# BiodataModular_007.net
KiCad netlist of a schematic drawn in EAGLE
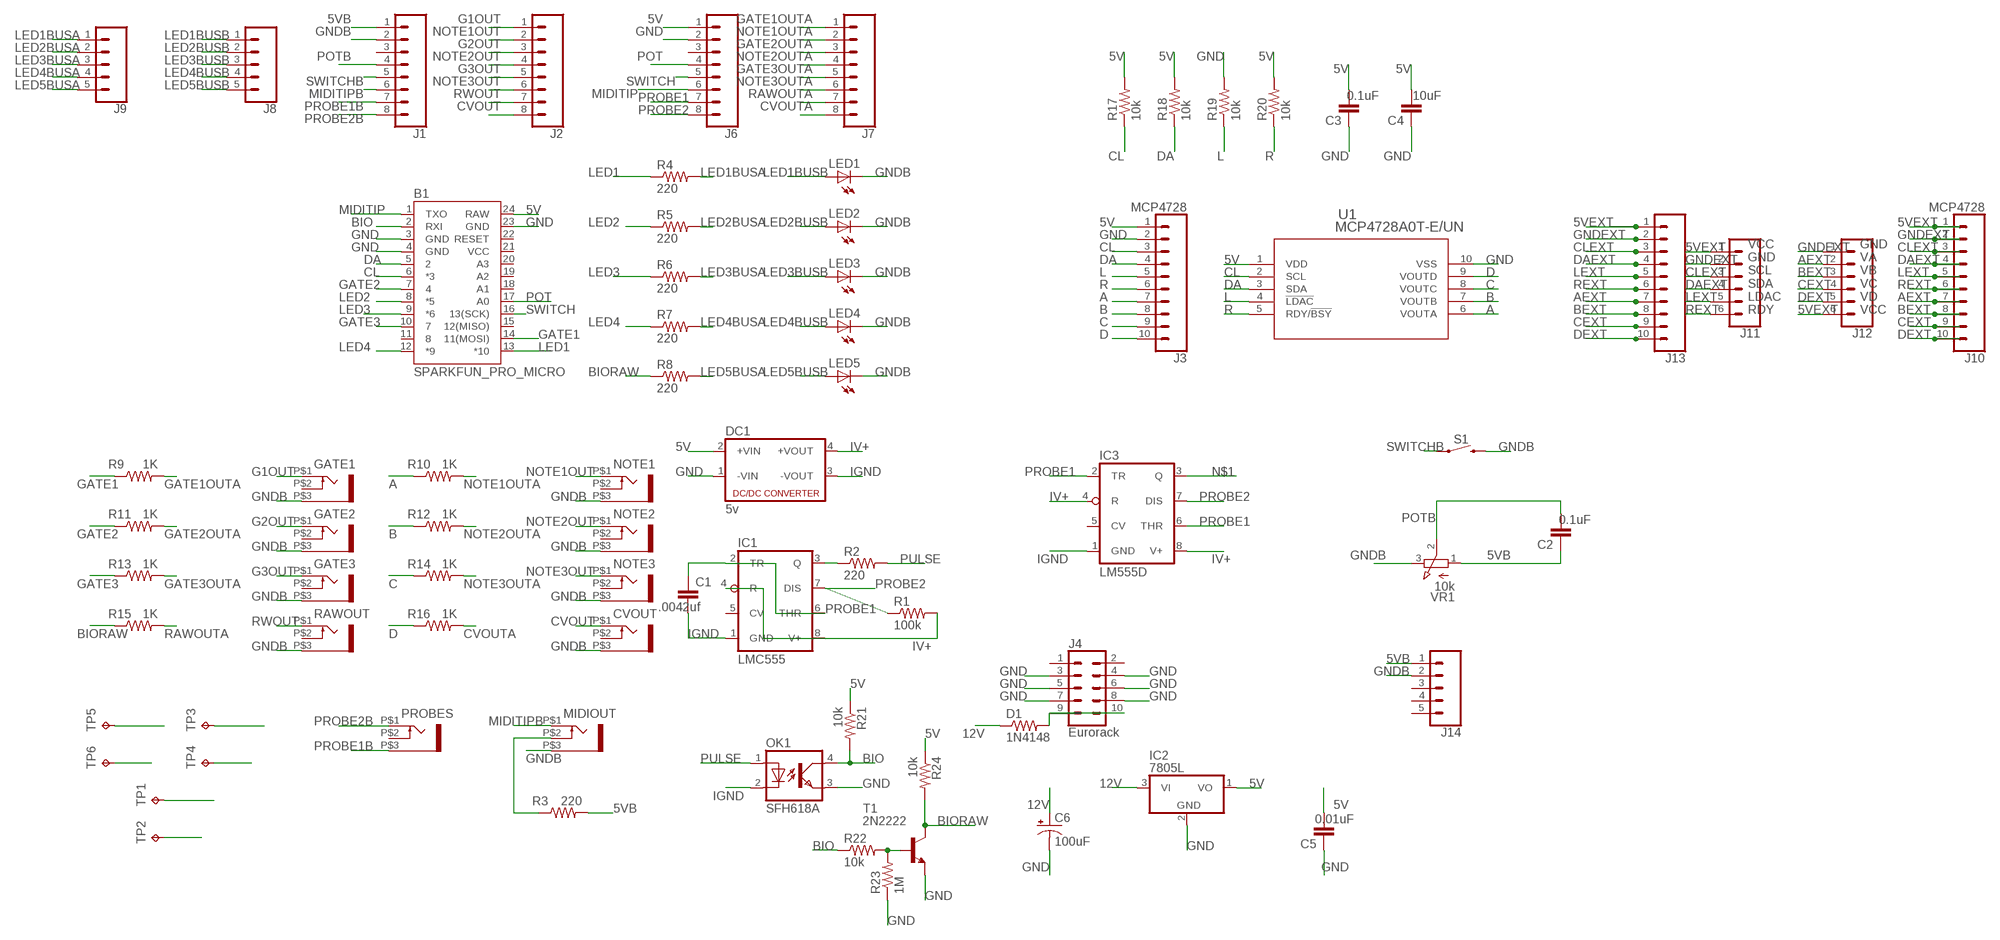
[diagram p0: schematic, sheet 1]

(export (version "E")
  (design (tool "Eeschema 10.0.6"))
  (components
    (comp (ref "B1")
      (value "SPARKFUN_PRO_MICRO")
      (footprint "eagle-import:SPARKFUN_PRO_MICRO")
      (libsource (lib "eagle-import") (part "SPARKFUN_PRO_MICRO"))
    )
    (comp (ref "C1")
      (value ".0042uf")
      (footprint "eagle-import:C2.5-2")
      (libsource (lib "eagle-import") (part "C2.5/2"))
    )
    (comp (ref "C2")
      (value "0.1uF")
      (footprint "eagle-import:C2.5-2")
      (libsource (lib "eagle-import") (part "C2.5/2"))
    )
    (comp (ref "C3")
      (value "0.1uF")
      (footprint "eagle-import:C2.5-2")
      (libsource (lib "eagle-import") (part "C2.5/2"))
    )
    (comp (ref "C4")
      (value "10uF")
      (footprint "eagle-import:C2.5-2")
      (libsource (lib "eagle-import") (part "C2.5/2"))
    )
    (comp (ref "C5")
      (value "0.01uF")
      (footprint "eagle-import:C2.5-2")
      (libsource (lib "eagle-import") (part "C2.5/2"))
    )
    (comp (ref "C6")
      (value "100uF")
      (footprint "eagle-import:B45181A")
      (libsource (lib "eagle-import") (part "CPOL-USB45181A"))
    )
    (comp (ref "CVOUT")
      (value "WQP-PJ301M-12_JACK")
      (footprint "eagle-import:WQP-PJ301M-12_JACK")
      (libsource (lib "eagle-import") (part "WQP-PJ301M-12_JACK"))
    )
    (comp (ref "D1")
      (value "1N4148")
      (footprint "eagle-import:0204V")
      (libsource (lib "eagle-import") (part "R-US_0204/2V"))
    )
    (comp (ref "DC1")
      (value "5v")
      (footprint "eagle-import:NME")
      (fields (field (name "MF") "C & D TECHNOLOGIES, INC") (field (name "MPN") "NME1205D"))
      (libsource (lib "eagle-import") (part "NME"))
    )
    (comp (ref "GATE1")
      (value "WQP-PJ301M-12_JACK")
      (footprint "eagle-import:WQP-PJ301M-12_JACK")
      (libsource (lib "eagle-import") (part "WQP-PJ301M-12_JACK"))
    )
    (comp (ref "GATE2")
      (value "WQP-PJ301M-12_JACK")
      (footprint "eagle-import:WQP-PJ301M-12_JACK")
      (libsource (lib "eagle-import") (part "WQP-PJ301M-12_JACK"))
    )
    (comp (ref "GATE3")
      (value "WQP-PJ301M-12_JACK")
      (footprint "eagle-import:WQP-PJ301M-12_JACK")
      (libsource (lib "eagle-import") (part "WQP-PJ301M-12_JACK"))
    )
    (comp (ref "IC1")
      (value "LMC555")
      (footprint "eagle-import:DIL08")
      (libsource (lib "eagle-import") (part "linear_555NLM"))
    )
    (comp (ref "IC2")
      (value "7805L")
      (footprint "eagle-import:TO92")
      (libsource (lib "eagle-import") (part "78L05"))
    )
    (comp (ref "IC3")
      (value "LM555D")
      (footprint "eagle-import:SO08")
      (libsource (lib "eagle-import") (part "555DLM"))
    )
    (comp (ref "J1")
      (value "CONN_08\"")
      (footprint "eagle-import:1X08")
      (libsource (lib "eagle-import") (part "CONN_08{dblquote}"))
    )
    (comp (ref "J2")
      (value "CONN_08\"")
      (footprint "eagle-import:1X08")
      (libsource (lib "eagle-import") (part "CONN_08{dblquote}"))
    )
    (comp (ref "J3")
      (value "MCP4728")
      (footprint "eagle-import:1X10")
      (libsource (lib "eagle-import") (part "CONN_10{dblquote}"))
    )
    (comp (ref "J4")
      (value "Eurorack")
      (footprint "eagle-import:2X5")
      (libsource (lib "eagle-import") (part "CONN_05X2PTH"))
    )
    (comp (ref "J6")
      (value "CONN_08\"")
      (footprint "eagle-import:1X08")
      (libsource (lib "eagle-import") (part "CONN_08{dblquote}"))
    )
    (comp (ref "J7")
      (value "CONN_08\"")
      (footprint "eagle-import:1X08")
      (libsource (lib "eagle-import") (part "CONN_08{dblquote}"))
    )
    (comp (ref "J8")
      (value "CONN_05")
      (footprint "eagle-import:1X05")
      (libsource (lib "eagle-import") (part "CONN_05"))
    )
    (comp (ref "J9")
      (value "CONN_05")
      (footprint "eagle-import:1X05")
      (libsource (lib "eagle-import") (part "CONN_05"))
    )
    (comp (ref "J10")
      (value "MCP4728")
      (footprint "eagle-import:1X10")
      (libsource (lib "eagle-import") (part "CONN_10{dblquote}"))
    )
    (comp (ref "J11")
      (value "CONN_06SILK_FEMALE_PTH")
      (footprint "eagle-import:1X06")
      (libsource (lib "eagle-import") (part "CONN_06SILK_FEMALE_PTH"))
    )
    (comp (ref "J12")
      (value "CONN_06SILK_FEMALE_PTH")
      (footprint "eagle-import:1X06")
      (libsource (lib "eagle-import") (part "CONN_06SILK_FEMALE_PTH"))
    )
    (comp (ref "J13")
      (value "CONN_10SMD_MALE")
      (footprint "eagle-import:1X10_SMD_MALE")
      (libsource (lib "eagle-import") (part "CONN_10SMD_MALE"))
    )
    (comp (ref "J14")
      (value "CONN_05")
      (footprint "eagle-import:1X05")
      (libsource (lib "eagle-import") (part "CONN_05"))
    )
    (comp (ref "LED1")
      (value "LED3MM")
      (footprint "eagle-import:LED3MM")
      (libsource (lib "eagle-import") (part "LED3MM"))
    )
    (comp (ref "LED2")
      (value "LED3MM")
      (footprint "eagle-import:LED3MM")
      (libsource (lib "eagle-import") (part "LED3MM"))
    )
    (comp (ref "LED3")
      (value "LED3MM")
      (footprint "eagle-import:LED3MM")
      (libsource (lib "eagle-import") (part "LED3MM"))
    )
    (comp (ref "LED4")
      (value "LED3MM")
      (footprint "eagle-import:LED3MM")
      (libsource (lib "eagle-import") (part "LED3MM"))
    )
    (comp (ref "LED5")
      (value "LED3MM")
      (footprint "eagle-import:LED3MM")
      (libsource (lib "eagle-import") (part "LED3MM"))
    )
    (comp (ref "MIDIOUT")
      (value "WQP-PJ301M-12_JACK")
      (footprint "eagle-import:WQP-PJ301M-12_JACK")
      (libsource (lib "eagle-import") (part "WQP-PJ301M-12_JACK"))
    )
    (comp (ref "NOTE1")
      (value "WQP-PJ301M-12_JACK")
      (footprint "eagle-import:WQP-PJ301M-12_JACK")
      (libsource (lib "eagle-import") (part "WQP-PJ301M-12_JACK"))
    )
    (comp (ref "NOTE2")
      (value "WQP-PJ301M-12_JACK")
      (footprint "eagle-import:WQP-PJ301M-12_JACK")
      (libsource (lib "eagle-import") (part "WQP-PJ301M-12_JACK"))
    )
    (comp (ref "NOTE3")
      (value "WQP-PJ301M-12_JACK")
      (footprint "eagle-import:WQP-PJ301M-12_JACK")
      (libsource (lib "eagle-import") (part "WQP-PJ301M-12_JACK"))
    )
    (comp (ref "OK1")
      (value "SFH618A")
      (footprint "eagle-import:DIP4")
      (fields (field (name "MF") "VISHAY/TELEFUNKEN") (field (name "MPN") "SFH618A-5"))
      (libsource (lib "eagle-import") (part "SFH618?A-5"))
    )
    (comp (ref "PROBES")
      (value "WQP-PJ301M-12_JACK")
      (footprint "eagle-import:WQP-PJ301M-12_JACK")
      (libsource (lib "eagle-import") (part "WQP-PJ301M-12_JACK"))
    )
    (comp (ref "R1")
      (value "100k")
      (footprint "eagle-import:0204V")
      (libsource (lib "eagle-import") (part "R-US_0204/2V"))
    )
    (comp (ref "R2")
      (value "220")
      (footprint "eagle-import:0204V")
      (libsource (lib "eagle-import") (part "R-US_0204/2V"))
    )
    (comp (ref "R3")
      (value "220")
      (footprint "eagle-import:0204V")
      (libsource (lib "eagle-import") (part "R-US_0204/2V"))
    )
    (comp (ref "R4")
      (value "220")
      (footprint "eagle-import:0204V")
      (libsource (lib "eagle-import") (part "R-US_0204/2V"))
    )
    (comp (ref "R5")
      (value "220")
      (footprint "eagle-import:0204V")
      (libsource (lib "eagle-import") (part "R-US_0204/2V"))
    )
    (comp (ref "R6")
      (value "220")
      (footprint "eagle-import:0204V")
      (libsource (lib "eagle-import") (part "R-US_0204/2V"))
    )
    (comp (ref "R7")
      (value "220")
      (footprint "eagle-import:0204V")
      (libsource (lib "eagle-import") (part "R-US_0204/2V"))
    )
    (comp (ref "R8")
      (value "220")
      (footprint "eagle-import:0204V")
      (libsource (lib "eagle-import") (part "R-US_0204/2V"))
    )
    (comp (ref "R9")
      (value "1K")
      (footprint "eagle-import:0204V")
      (libsource (lib "eagle-import") (part "R-US_0204/2V"))
    )
    (comp (ref "R10")
      (value "1K")
      (footprint "eagle-import:0204V")
      (libsource (lib "eagle-import") (part "R-US_0204/2V"))
    )
    (comp (ref "R11")
      (value "1K")
      (footprint "eagle-import:0204V")
      (libsource (lib "eagle-import") (part "R-US_0204/2V"))
    )
    (comp (ref "R12")
      (value "1K")
      (footprint "eagle-import:0204V")
      (libsource (lib "eagle-import") (part "R-US_0204/2V"))
    )
    (comp (ref "R13")
      (value "1K")
      (footprint "eagle-import:0204V")
      (libsource (lib "eagle-import") (part "R-US_0204/2V"))
    )
    (comp (ref "R14")
      (value "1K")
      (footprint "eagle-import:0204V")
      (libsource (lib "eagle-import") (part "R-US_0204/2V"))
    )
    (comp (ref "R15")
      (value "1K")
      (footprint "eagle-import:0204V")
      (libsource (lib "eagle-import") (part "R-US_0204/2V"))
    )
    (comp (ref "R16")
      (value "1K")
      (footprint "eagle-import:0204V")
      (libsource (lib "eagle-import") (part "R-US_0204/2V"))
    )
    (comp (ref "R17")
      (value "10k")
      (footprint "eagle-import:0204V")
      (libsource (lib "eagle-import") (part "R-US_0204/2V"))
    )
    (comp (ref "R18")
      (value "10k")
      (footprint "eagle-import:0204V")
      (libsource (lib "eagle-import") (part "R-US_0204/2V"))
    )
    (comp (ref "R19")
      (value "10k")
      (footprint "eagle-import:0204V")
      (libsource (lib "eagle-import") (part "R-US_0204/2V"))
    )
    (comp (ref "R20")
      (value "10k")
      (footprint "eagle-import:0204V")
      (libsource (lib "eagle-import") (part "R-US_0204/2V"))
    )
    (comp (ref "R21")
      (value "10k")
      (footprint "eagle-import:0204V")
      (libsource (lib "eagle-import") (part "R-US_0204/2V"))
    )
    (comp (ref "R22")
      (value "10k")
      (footprint "eagle-import:0204V")
      (libsource (lib "eagle-import") (part "R-US_0204/2V"))
    )
    (comp (ref "R23")
      (value "1M")
      (footprint "eagle-import:0204V")
      (libsource (lib "eagle-import") (part "R-US_0204/2V"))
    )
    (comp (ref "R24")
      (value "10k")
      (footprint "eagle-import:0204V")
      (libsource (lib "eagle-import") (part "R-US_0204/2V"))
    )
    (comp (ref "RAWOUT")
      (value "WQP-PJ301M-12_JACK")
      (footprint "eagle-import:WQP-PJ301M-12_JACK")
      (libsource (lib "eagle-import") (part "WQP-PJ301M-12_JACK"))
    )
    (comp (ref "S1")
      (value "MOMENTARY-SWITCH-SPST-PTH-6.0MM")
      (footprint "eagle-import:TACTILE_SWITCH_PTH_6.0MM")
      (libsource (lib "eagle-import") (part "MOMENTARY-SWITCH-SPST-PTH-6.0MM"))
    )
    (comp (ref "T1")
      (value "2N2222")
      (footprint "eagle-import:TO92-EBC-OVAL")
      (libsource (lib "eagle-import") (part "2N2222"))
    )
    (comp (ref "TP1")
      (value "TPB1,27")
      (footprint "eagle-import:B1,27")
      (libsource (lib "eagle-import") (part "TPB1,27"))
    )
    (comp (ref "TP2")
      (value "TPB1,27")
      (footprint "eagle-import:B1,27")
      (libsource (lib "eagle-import") (part "TPB1,27"))
    )
    (comp (ref "TP3")
      (value "TPB1,27")
      (footprint "eagle-import:B1,27")
      (libsource (lib "eagle-import") (part "TPB1,27"))
    )
    (comp (ref "TP4")
      (value "TPB1,27")
      (footprint "eagle-import:B1,27")
      (libsource (lib "eagle-import") (part "TPB1,27"))
    )
    (comp (ref "TP5")
      (value "TPB1,27")
      (footprint "eagle-import:B1,27")
      (libsource (lib "eagle-import") (part "TPB1,27"))
    )
    (comp (ref "TP6")
      (value "TPB1,27")
      (footprint "eagle-import:B1,27")
      (libsource (lib "eagle-import") (part "TPB1,27"))
    )
    (comp (ref "U1")
      (value "MCP4728A0T-E/UN")
      (footprint "eagle-import:MSOP10_MC")
      (fields (field (name "MANUFACTURER_PART_NUMBER") "MCP4728A0TEUN"))
      (libsource (lib "eagle-import") (part "MCP4728A0T-E/UN"))
    )
    (comp (ref "VR1")
      (value "10k")
      (footprint "eagle-import:EVUF")
      (libsource (lib "eagle-import") (part "EVUAF2"))
    )
  )
  (nets
    (net (code "1") (name "/5V") (class "Default")
      (node (ref "B1") (pin "24") (pinfunction "RAW_24") (pintype "power_in"))
      (node (ref "C3") (pin "2") (pinfunction "2_2") (pintype "passive"))
      (node (ref "C4") (pin "2") (pinfunction "2_2") (pintype "passive"))
      (node (ref "C5") (pin "2") (pinfunction "2_2") (pintype "passive"))
      (node (ref "DC1") (pin "2") (pinfunction "+VIN_2") (pintype "passive"))
      (node (ref "IC2") (pin "1") (pinfunction "VO_1") (pintype "passive"))
      (node (ref "J3") (pin "1") (pinfunction "1_1") (pintype "passive"))
      (node (ref "J6") (pin "1") (pinfunction "1_1") (pintype "passive"))
      (node (ref "R17") (pin "2") (pinfunction "2_2") (pintype "passive"))
      (node (ref "R18") (pin "2") (pinfunction "2_2") (pintype "passive"))
      (node (ref "R20") (pin "2") (pinfunction "2_2") (pintype "passive"))
      (node (ref "R21") (pin "1") (pinfunction "1_1") (pintype "passive"))
      (node (ref "R24") (pin "1") (pinfunction "1_1") (pintype "passive"))
      (node (ref "U1") (pin "1") (pinfunction "VDD_1") (pintype "power_in"))
    )
    (net (code "2") (name "/5VB") (class "Default")
      (node (ref "C2") (pin "1") (pinfunction "1_1") (pintype "passive"))
      (node (ref "J1") (pin "1") (pinfunction "1_1") (pintype "passive"))
      (node (ref "J14") (pin "1") (pinfunction "1_1") (pintype "passive"))
      (node (ref "R3") (pin "2") (pinfunction "2_2") (pintype "passive"))
      (node (ref "VR1") (pin "1") (pinfunction "A_1") (pintype "passive"))
    )
    (net (code "3") (name "/5VEXT") (class "Default")
      (node (ref "J10") (pin "1") (pinfunction "1_1") (pintype "passive"))
      (node (ref "J11") (pin "1") (pinfunction "1_1") (pintype "passive"))
      (node (ref "J12") (pin "6") (pinfunction "6_6") (pintype "passive"))
      (node (ref "J13") (pin "1") (pinfunction "1_1") (pintype "passive"))
    )
    (net (code "4") (name "/12V") (class "Default")
      (node (ref "C6") (pin "+") (pinfunction "+_+") (pintype "passive"))
      (node (ref "D1") (pin "1") (pinfunction "1_1") (pintype "passive"))
      (node (ref "IC2") (pin "3") (pinfunction "VI_3") (pintype "input"))
    )
    (net (code "5") (name "/A") (class "Default")
      (node (ref "J3") (pin "7") (pinfunction "7_7") (pintype "passive"))
      (node (ref "R10") (pin "1") (pinfunction "1_1") (pintype "passive"))
      (node (ref "U1") (pin "6") (pinfunction "VOUTA_6") (pintype "output"))
    )
    (net (code "6") (name "/AEXT") (class "Default")
      (node (ref "J10") (pin "7") (pinfunction "7_7") (pintype "passive"))
      (node (ref "J12") (pin "2") (pinfunction "2_2") (pintype "passive"))
      (node (ref "J13") (pin "7") (pinfunction "7_7") (pintype "passive"))
    )
    (net (code "7") (name "/B") (class "Default")
      (node (ref "J3") (pin "8") (pinfunction "8_8") (pintype "passive"))
      (node (ref "R12") (pin "1") (pinfunction "1_1") (pintype "passive"))
      (node (ref "U1") (pin "7") (pinfunction "VOUTB_7") (pintype "output"))
    )
    (net (code "8") (name "/BEXT") (class "Default")
      (node (ref "J10") (pin "8") (pinfunction "8_8") (pintype "passive"))
      (node (ref "J12") (pin "3") (pinfunction "3_3") (pintype "passive"))
      (node (ref "J13") (pin "8") (pinfunction "8_8") (pintype "passive"))
    )
    (net (code "9") (name "/BIO") (class "Default")
      (node (ref "B1") (pin "2") (pinfunction "RXI_2") (pintype "bidirectional"))
      (node (ref "OK1") (pin "4") (pinfunction "COL_4") (pintype "passive"))
      (node (ref "R21") (pin "2") (pinfunction "2_2") (pintype "passive"))
      (node (ref "R22") (pin "1") (pinfunction "1_1") (pintype "passive"))
    )
    (net (code "10") (name "/BIORAW") (class "Default")
      (node (ref "R15") (pin "1") (pinfunction "1_1") (pintype "passive"))
      (node (ref "R24") (pin "2") (pinfunction "2_2") (pintype "passive"))
      (node (ref "R8") (pin "1") (pinfunction "1_1") (pintype "passive"))
      (node (ref "T1") (pin "C") (pinfunction "C_C") (pintype "passive"))
    )
    (net (code "11") (name "/C") (class "Default")
      (node (ref "J3") (pin "9") (pinfunction "9_9") (pintype "passive"))
      (node (ref "R14") (pin "1") (pinfunction "1_1") (pintype "passive"))
      (node (ref "U1") (pin "8") (pinfunction "VOUTC_8") (pintype "output"))
    )
    (net (code "12") (name "/CEXT") (class "Default")
      (node (ref "J10") (pin "9") (pinfunction "9_9") (pintype "passive"))
      (node (ref "J12") (pin "4") (pinfunction "4_4") (pintype "passive"))
      (node (ref "J13") (pin "9") (pinfunction "9_9") (pintype "passive"))
    )
    (net (code "13") (name "/CL") (class "Default")
      (node (ref "B1") (pin "6") (pinfunction "*3_6") (pintype "bidirectional"))
      (node (ref "J3") (pin "3") (pinfunction "3_3") (pintype "passive"))
      (node (ref "R17") (pin "1") (pinfunction "1_1") (pintype "passive"))
      (node (ref "U1") (pin "2") (pinfunction "SCL_2") (pintype "input"))
    )
    (net (code "14") (name "/CLEXT") (class "Default")
      (node (ref "J10") (pin "3") (pinfunction "3_3") (pintype "passive"))
      (node (ref "J11") (pin "3") (pinfunction "3_3") (pintype "passive"))
      (node (ref "J13") (pin "3") (pinfunction "3_3") (pintype "passive"))
    )
    (net (code "15") (name "/CVOUT") (class "Default")
      (node (ref "CVOUT") (pin "P$1") (pinfunction "2_P$1") (pintype "passive"))
      (node (ref "J2") (pin "8") (pinfunction "8_8") (pintype "passive"))
    )
    (net (code "16") (name "/CVOUTA") (class "Default")
      (node (ref "J7") (pin "8") (pinfunction "8_8") (pintype "passive"))
      (node (ref "R16") (pin "2") (pinfunction "2_2") (pintype "passive"))
    )
    (net (code "17") (name "/D") (class "Default")
      (node (ref "J3") (pin "10") (pinfunction "10_10") (pintype "passive"))
      (node (ref "R16") (pin "1") (pinfunction "1_1") (pintype "passive"))
      (node (ref "U1") (pin "9") (pinfunction "VOUTD_9") (pintype "output"))
    )
    (net (code "18") (name "/DA") (class "Default")
      (node (ref "B1") (pin "5") (pinfunction "2_5") (pintype "bidirectional"))
      (node (ref "J3") (pin "4") (pinfunction "4_4") (pintype "passive"))
      (node (ref "R18") (pin "1") (pinfunction "1_1") (pintype "passive"))
      (node (ref "U1") (pin "3") (pinfunction "SDA_3") (pintype "bidirectional"))
    )
    (net (code "19") (name "/DAEXT") (class "Default")
      (node (ref "J10") (pin "4") (pinfunction "4_4") (pintype "passive"))
      (node (ref "J11") (pin "4") (pinfunction "4_4") (pintype "passive"))
      (node (ref "J13") (pin "4") (pinfunction "4_4") (pintype "passive"))
    )
    (net (code "20") (name "/DEXT") (class "Default")
      (node (ref "J10") (pin "10") (pinfunction "10_10") (pintype "passive"))
      (node (ref "J12") (pin "5") (pinfunction "5_5") (pintype "passive"))
      (node (ref "J13") (pin "10") (pinfunction "10_10") (pintype "passive"))
    )
    (net (code "21") (name "/G1OUT") (class "Default")
      (node (ref "GATE1") (pin "P$1") (pinfunction "2_P$1") (pintype "passive"))
      (node (ref "J2") (pin "1") (pinfunction "1_1") (pintype "passive"))
    )
    (net (code "22") (name "/G2OUT") (class "Default")
      (node (ref "GATE2") (pin "P$1") (pinfunction "2_P$1") (pintype "passive"))
      (node (ref "J2") (pin "3") (pinfunction "3_3") (pintype "passive"))
    )
    (net (code "23") (name "/G3OUT") (class "Default")
      (node (ref "GATE3") (pin "P$1") (pinfunction "2_P$1") (pintype "passive"))
      (node (ref "J2") (pin "5") (pinfunction "5_5") (pintype "passive"))
    )
    (net (code "24") (name "/GATE1") (class "Default")
      (node (ref "B1") (pin "14") (pinfunction "11(MOSI)_14") (pintype "bidirectional"))
      (node (ref "R9") (pin "1") (pinfunction "1_1") (pintype "passive"))
    )
    (net (code "25") (name "/GATE1OUTA") (class "Default")
      (node (ref "J7") (pin "1") (pinfunction "1_1") (pintype "passive"))
      (node (ref "R9") (pin "2") (pinfunction "2_2") (pintype "passive"))
    )
    (net (code "26") (name "/GATE2") (class "Default")
      (node (ref "B1") (pin "7") (pinfunction "4_7") (pintype "bidirectional"))
      (node (ref "R11") (pin "1") (pinfunction "1_1") (pintype "passive"))
    )
    (net (code "27") (name "/GATE2OUTA") (class "Default")
      (node (ref "J7") (pin "3") (pinfunction "3_3") (pintype "passive"))
      (node (ref "R11") (pin "2") (pinfunction "2_2") (pintype "passive"))
    )
    (net (code "28") (name "/GATE3") (class "Default")
      (node (ref "B1") (pin "10") (pinfunction "7_10") (pintype "bidirectional"))
      (node (ref "R13") (pin "1") (pinfunction "1_1") (pintype "passive"))
    )
    (net (code "29") (name "/GATE3OUTA") (class "Default")
      (node (ref "J7") (pin "5") (pinfunction "5_5") (pintype "passive"))
      (node (ref "R13") (pin "2") (pinfunction "2_2") (pintype "passive"))
    )
    (net (code "30") (name "/GND") (class "Default")
      (node (ref "B1") (pin "23") (pinfunction "GND_23") (pintype "power_in"))
      (node (ref "B1") (pin "3") (pinfunction "GND_3") (pintype "power_in"))
      (node (ref "B1") (pin "4") (pinfunction "GND_4") (pintype "power_in"))
      (node (ref "C3") (pin "1") (pinfunction "1_1") (pintype "passive"))
      (node (ref "C4") (pin "1") (pinfunction "1_1") (pintype "passive"))
      (node (ref "C5") (pin "1") (pinfunction "1_1") (pintype "passive"))
      (node (ref "C6") (pin "-") (pinfunction "-_-") (pintype "passive"))
      (node (ref "DC1") (pin "1") (pinfunction "-VIN_1") (pintype "passive"))
      (node (ref "IC2") (pin "2") (pinfunction "GND_2") (pintype "passive"))
      (node (ref "J3") (pin "2") (pinfunction "2_2") (pintype "passive"))
      (node (ref "J4") (pin "3") (pinfunction "3_3") (pintype "passive"))
      (node (ref "J4") (pin "4") (pinfunction "4_4") (pintype "passive"))
      (node (ref "J4") (pin "5") (pinfunction "5_5") (pintype "passive"))
      (node (ref "J4") (pin "6") (pinfunction "6_6") (pintype "passive"))
      (node (ref "J4") (pin "7") (pinfunction "7_7") (pintype "passive"))
      (node (ref "J4") (pin "8") (pinfunction "8_8") (pintype "passive"))
      (node (ref "J6") (pin "2") (pinfunction "2_2") (pintype "passive"))
      (node (ref "OK1") (pin "3") (pinfunction "EMIT_3") (pintype "passive"))
      (node (ref "R19") (pin "2") (pinfunction "2_2") (pintype "passive"))
      (node (ref "R23") (pin "1") (pinfunction "1_1") (pintype "passive"))
      (node (ref "T1") (pin "E") (pinfunction "E_E") (pintype "passive"))
      (node (ref "U1") (pin "10") (pinfunction "VSS_10") (pintype "power_in"))
    )
    (net (code "31") (name "/GNDB") (class "Default")
      (node (ref "CVOUT") (pin "P$3") (pinfunction "1_P$3") (pintype "passive"))
      (node (ref "GATE1") (pin "P$3") (pinfunction "1_P$3") (pintype "passive"))
      (node (ref "GATE2") (pin "P$3") (pinfunction "1_P$3") (pintype "passive"))
      (node (ref "GATE3") (pin "P$3") (pinfunction "1_P$3") (pintype "passive"))
      (node (ref "J1") (pin "2") (pinfunction "2_2") (pintype "passive"))
      (node (ref "J14") (pin "2") (pinfunction "2_2") (pintype "passive"))
      (node (ref "LED1") (pin "K") (pinfunction "C_K") (pintype "passive"))
      (node (ref "LED2") (pin "K") (pinfunction "C_K") (pintype "passive"))
      (node (ref "LED3") (pin "K") (pinfunction "C_K") (pintype "passive"))
      (node (ref "LED4") (pin "K") (pinfunction "C_K") (pintype "passive"))
      (node (ref "LED5") (pin "K") (pinfunction "C_K") (pintype "passive"))
      (node (ref "MIDIOUT") (pin "P$3") (pinfunction "1_P$3") (pintype "passive"))
      (node (ref "NOTE1") (pin "P$3") (pinfunction "1_P$3") (pintype "passive"))
      (node (ref "NOTE2") (pin "P$3") (pinfunction "1_P$3") (pintype "passive"))
      (node (ref "NOTE3") (pin "P$3") (pinfunction "1_P$3") (pintype "passive"))
      (node (ref "RAWOUT") (pin "P$3") (pinfunction "1_P$3") (pintype "passive"))
      (node (ref "S1") (pin "3") (pinfunction "2_3") (pintype "passive"))
      (node (ref "VR1") (pin "3") (pinfunction "E_3") (pintype "passive"))
    )
    (net (code "32") (name "/GNDEXT") (class "Default")
      (node (ref "J10") (pin "2") (pinfunction "2_2") (pintype "passive"))
      (node (ref "J11") (pin "2") (pinfunction "2_2") (pintype "passive"))
      (node (ref "J12") (pin "1") (pinfunction "1_1") (pintype "passive"))
      (node (ref "J13") (pin "2") (pinfunction "2_2") (pintype "passive"))
    )
    (net (code "33") (name "/IGND") (class "Default")
      (node (ref "C1") (pin "2") (pinfunction "2_2") (pintype "passive"))
      (node (ref "DC1") (pin "3") (pinfunction "-VOUT_3") (pintype "passive"))
      (node (ref "IC1") (pin "1") (pinfunction "GND_1") (pintype "power_in"))
      (node (ref "IC3") (pin "1") (pinfunction "GND_1") (pintype "power_in"))
      (node (ref "OK1") (pin "2") (pinfunction "C_2") (pintype "passive"))
    )
    (net (code "34") (name "/IV+") (class "Default")
      (node (ref "DC1") (pin "4") (pinfunction "+VOUT_4") (pintype "passive"))
      (node (ref "IC1") (pin "4") (pinfunction "R_4") (pintype "input"))
      (node (ref "IC1") (pin "8") (pinfunction "V+_8") (pintype "power_in"))
      (node (ref "IC3") (pin "4") (pinfunction "R_4") (pintype "input"))
      (node (ref "IC3") (pin "8") (pinfunction "V+_8") (pintype "power_in"))
      (node (ref "R1") (pin "2") (pinfunction "2_2") (pintype "passive"))
    )
    (net (code "35") (name "/L") (class "Default")
      (node (ref "J3") (pin "5") (pinfunction "5_5") (pintype "passive"))
      (node (ref "R19") (pin "1") (pinfunction "1_1") (pintype "passive"))
      (node (ref "U1") (pin "4") (pinfunction "~{LDAC}_4") (pintype "input"))
    )
    (net (code "36") (name "/LED1") (class "Default")
      (node (ref "B1") (pin "13") (pinfunction "*10_13") (pintype "bidirectional"))
      (node (ref "R4") (pin "1") (pinfunction "1_1") (pintype "passive"))
    )
    (net (code "37") (name "/LED1BUSA") (class "Default")
      (node (ref "J9") (pin "1") (pinfunction "1_1") (pintype "passive"))
      (node (ref "R4") (pin "2") (pinfunction "2_2") (pintype "passive"))
    )
    (net (code "38") (name "/LED1BUSB") (class "Default")
      (node (ref "J8") (pin "1") (pinfunction "1_1") (pintype "passive"))
      (node (ref "LED1") (pin "A") (pinfunction "A_A") (pintype "passive"))
    )
    (net (code "39") (name "/LED2") (class "Default")
      (node (ref "B1") (pin "8") (pinfunction "*5_8") (pintype "bidirectional"))
      (node (ref "R5") (pin "1") (pinfunction "1_1") (pintype "passive"))
    )
    (net (code "40") (name "/LED2BUSA") (class "Default")
      (node (ref "J9") (pin "2") (pinfunction "2_2") (pintype "passive"))
      (node (ref "R5") (pin "2") (pinfunction "2_2") (pintype "passive"))
    )
    (net (code "41") (name "/LED2BUSB") (class "Default")
      (node (ref "J8") (pin "2") (pinfunction "2_2") (pintype "passive"))
      (node (ref "LED2") (pin "A") (pinfunction "A_A") (pintype "passive"))
    )
    (net (code "42") (name "/LED3") (class "Default")
      (node (ref "B1") (pin "9") (pinfunction "*6_9") (pintype "bidirectional"))
      (node (ref "R6") (pin "1") (pinfunction "1_1") (pintype "passive"))
    )
    (net (code "43") (name "/LED3BUSA") (class "Default")
      (node (ref "J9") (pin "3") (pinfunction "3_3") (pintype "passive"))
      (node (ref "R6") (pin "2") (pinfunction "2_2") (pintype "passive"))
    )
    (net (code "44") (name "/LED3BUSB") (class "Default")
      (node (ref "J8") (pin "3") (pinfunction "3_3") (pintype "passive"))
      (node (ref "LED3") (pin "A") (pinfunction "A_A") (pintype "passive"))
    )
    (net (code "45") (name "/LED4") (class "Default")
      (node (ref "B1") (pin "12") (pinfunction "*9_12") (pintype "bidirectional"))
      (node (ref "R7") (pin "1") (pinfunction "1_1") (pintype "passive"))
    )
    (net (code "46") (name "/LED4BUSA") (class "Default")
      (node (ref "J9") (pin "4") (pinfunction "4_4") (pintype "passive"))
      (node (ref "R7") (pin "2") (pinfunction "2_2") (pintype "passive"))
    )
    (net (code "47") (name "/LED4BUSB") (class "Default")
      (node (ref "J8") (pin "4") (pinfunction "4_4") (pintype "passive"))
      (node (ref "LED4") (pin "A") (pinfunction "A_A") (pintype "passive"))
    )
    (net (code "48") (name "/LED5BUSA") (class "Default")
      (node (ref "J9") (pin "5") (pinfunction "5_5") (pintype "passive"))
      (node (ref "R8") (pin "2") (pinfunction "2_2") (pintype "passive"))
    )
    (net (code "49") (name "/LED5BUSB") (class "Default")
      (node (ref "J8") (pin "5") (pinfunction "5_5") (pintype "passive"))
      (node (ref "LED5") (pin "A") (pinfunction "A_A") (pintype "passive"))
    )
    (net (code "50") (name "/LEXT") (class "Default")
      (node (ref "J10") (pin "5") (pinfunction "5_5") (pintype "passive"))
      (node (ref "J11") (pin "5") (pinfunction "5_5") (pintype "passive"))
      (node (ref "J13") (pin "5") (pinfunction "5_5") (pintype "passive"))
    )
    (net (code "51") (name "/MIDITIP") (class "Default")
      (node (ref "B1") (pin "1") (pinfunction "TXO_1") (pintype "bidirectional"))
      (node (ref "J6") (pin "6") (pinfunction "6_6") (pintype "passive"))
    )
    (net (code "52") (name "/MIDITIPB") (class "Default")
      (node (ref "J1") (pin "6") (pinfunction "6_6") (pintype "passive"))
      (node (ref "MIDIOUT") (pin "P$1") (pinfunction "2_P$1") (pintype "passive"))
    )
    (net (code "53") (name "/N$1") (class "Default")
      (node (ref "IC1") (pin "3") (pinfunction "Q_3") (pintype "output"))
      (node (ref "IC3") (pin "3") (pinfunction "Q_3") (pintype "output"))
      (node (ref "R2") (pin "1") (pinfunction "1_1") (pintype "passive"))
    )
    (net (code "54") (name "/NOTE1OUT") (class "Default")
      (node (ref "J2") (pin "2") (pinfunction "2_2") (pintype "passive"))
      (node (ref "NOTE1") (pin "P$1") (pinfunction "2_P$1") (pintype "passive"))
    )
    (net (code "55") (name "/NOTE1OUTA") (class "Default")
      (node (ref "J7") (pin "2") (pinfunction "2_2") (pintype "passive"))
      (node (ref "R10") (pin "2") (pinfunction "2_2") (pintype "passive"))
    )
    (net (code "56") (name "/NOTE2OUT") (class "Default")
      (node (ref "J2") (pin "4") (pinfunction "4_4") (pintype "passive"))
      (node (ref "NOTE2") (pin "P$1") (pinfunction "2_P$1") (pintype "passive"))
    )
    (net (code "57") (name "/NOTE2OUTA") (class "Default")
      (node (ref "J7") (pin "4") (pinfunction "4_4") (pintype "passive"))
      (node (ref "R12") (pin "2") (pinfunction "2_2") (pintype "passive"))
    )
    (net (code "58") (name "/NOTE3OUT") (class "Default")
      (node (ref "J2") (pin "6") (pinfunction "6_6") (pintype "passive"))
      (node (ref "NOTE3") (pin "P$1") (pinfunction "2_P$1") (pintype "passive"))
    )
    (net (code "59") (name "/NOTE3OUTA") (class "Default")
      (node (ref "J7") (pin "6") (pinfunction "6_6") (pintype "passive"))
      (node (ref "R14") (pin "2") (pinfunction "2_2") (pintype "passive"))
    )
    (net (code "60") (name "/POT") (class "Default")
      (node (ref "B1") (pin "17") (pinfunction "A0_17") (pintype "bidirectional"))
      (node (ref "J6") (pin "4") (pinfunction "4_4") (pintype "passive"))
    )
    (net (code "61") (name "/POTB") (class "Default")
      (node (ref "C2") (pin "2") (pinfunction "2_2") (pintype "passive"))
      (node (ref "J1") (pin "4") (pinfunction "4_4") (pintype "passive"))
      (node (ref "VR1") (pin "2") (pinfunction "S_2") (pintype "passive"))
    )
    (net (code "62") (name "/PROBE1") (class "Default")
      (node (ref "C1") (pin "1") (pinfunction "1_1") (pintype "passive"))
      (node (ref "IC1") (pin "2") (pinfunction "TR_2") (pintype "input"))
      (node (ref "IC1") (pin "6") (pinfunction "THR_6") (pintype "input"))
      (node (ref "IC3") (pin "2") (pinfunction "TR_2") (pintype "input"))
      (node (ref "IC3") (pin "6") (pinfunction "THR_6") (pintype "input"))
      (node (ref "J6") (pin "7") (pinfunction "7_7") (pintype "passive"))
    )
    (net (code "63") (name "/PROBE1B") (class "Default")
      (node (ref "J1") (pin "7") (pinfunction "7_7") (pintype "passive"))
      (node (ref "PROBES") (pin "P$3") (pinfunction "1_P$3") (pintype "passive"))
      (node (ref "TP2") (pin "TP") (pinfunction "TP_TP") (pintype "input"))
    )
    (net (code "64") (name "/PROBE2") (class "Default")
      (node (ref "IC1") (pin "7") (pinfunction "DIS_7") (pintype "input"))
      (node (ref "IC3") (pin "7") (pinfunction "DIS_7") (pintype "input"))
      (node (ref "J6") (pin "8") (pinfunction "8_8") (pintype "passive"))
      (node (ref "R1") (pin "1") (pinfunction "1_1") (pintype "passive"))
    )
    (net (code "65") (name "/PROBE2B") (class "Default")
      (node (ref "J1") (pin "8") (pinfunction "8_8") (pintype "passive"))
      (node (ref "PROBES") (pin "P$1") (pinfunction "2_P$1") (pintype "passive"))
      (node (ref "TP1") (pin "TP") (pinfunction "TP_TP") (pintype "input"))
    )
    (net (code "66") (name "/PULSE") (class "Default")
      (node (ref "OK1") (pin "1") (pinfunction "A_1") (pintype "passive"))
      (node (ref "R2") (pin "2") (pinfunction "2_2") (pintype "passive"))
    )
    (net (code "67") (name "/R") (class "Default")
      (node (ref "J3") (pin "6") (pinfunction "6_6") (pintype "passive"))
      (node (ref "R20") (pin "1") (pinfunction "1_1") (pintype "passive"))
      (node (ref "U1") (pin "5") (pinfunction "RDY/~{BSY}_5") (pintype "output"))
    )
    (net (code "68") (name "/RAWOUTA") (class "Default")
      (node (ref "J7") (pin "7") (pinfunction "7_7") (pintype "passive"))
      (node (ref "R15") (pin "2") (pinfunction "2_2") (pintype "passive"))
    )
    (net (code "69") (name "/REXT") (class "Default")
      (node (ref "J10") (pin "6") (pinfunction "6_6") (pintype "passive"))
      (node (ref "J11") (pin "6") (pinfunction "6_6") (pintype "passive"))
      (node (ref "J13") (pin "6") (pinfunction "6_6") (pintype "passive"))
    )
    (net (code "70") (name "/RWOUT") (class "Default")
      (node (ref "J2") (pin "7") (pinfunction "7_7") (pintype "passive"))
      (node (ref "RAWOUT") (pin "P$1") (pinfunction "2_P$1") (pintype "passive"))
    )
    (net (code "71") (name "/SWITCH") (class "Default")
      (node (ref "B1") (pin "16") (pinfunction "13(SCK)_16") (pintype "bidirectional"))
      (node (ref "J6") (pin "5") (pinfunction "5_5") (pintype "passive"))
    )
    (net (code "72") (name "/SWITCHB") (class "Default")
      (node (ref "J1") (pin "5") (pinfunction "5_5") (pintype "passive"))
      (node (ref "S1") (pin "1") (pinfunction "1_1") (pintype "passive"))
    )
    (net (code "73") (name "/VCC") (class "Default")
      (node (ref "B1") (pin "21") (pinfunction "VCC_21") (pintype "power_in"))
    )
    (net (code "74") (name "Net-(D1-Pad2)") (class "Default")
      (node (ref "D1") (pin "2") (pinfunction "2_2") (pintype "passive"))
      (node (ref "J4") (pin "10") (pinfunction "10_10") (pintype "passive"))
      (node (ref "J4") (pin "9") (pinfunction "9_9") (pintype "passive"))
    )
    (net (code "75") (name "Net-(MIDIOUT-3)") (class "Default")
      (node (ref "MIDIOUT") (pin "P$2") (pinfunction "3_P$2") (pintype "passive"))
      (node (ref "R3") (pin "1") (pinfunction "1_1") (pintype "passive"))
    )
    (net (code "76") (name "Net-(R22-Pad2)") (class "Default")
      (node (ref "R22") (pin "2") (pinfunction "2_2") (pintype "passive"))
      (node (ref "R23") (pin "2") (pinfunction "2_2") (pintype "passive"))
      (node (ref "T1") (pin "B") (pinfunction "B_B") (pintype "passive"))
    )
    (net (code "77") (name "unconnected-(B1-8-Pad11)") (class "Default")
      (node (ref "B1") (pin "11") (pinfunction "8_11") (pintype "bidirectional"))
    )
    (net (code "78") (name "unconnected-(B1-12(MISO)-Pad15)") (class "Default")
      (node (ref "B1") (pin "15") (pinfunction "12(MISO)_15") (pintype "bidirectional"))
    )
    (net (code "79") (name "unconnected-(B1-A1-Pad18)") (class "Default")
      (node (ref "B1") (pin "18") (pinfunction "A1_18") (pintype "bidirectional"))
    )
    (net (code "80") (name "unconnected-(B1-A2-Pad19)") (class "Default")
      (node (ref "B1") (pin "19") (pinfunction "A2_19") (pintype "bidirectional"))
    )
    (net (code "81") (name "unconnected-(B1-A3-Pad20)") (class "Default")
      (node (ref "B1") (pin "20") (pinfunction "A3_20") (pintype "bidirectional"))
    )
    (net (code "82") (name "unconnected-(B1-RESET-Pad22)") (class "Default")
      (node (ref "B1") (pin "22") (pinfunction "RESET_22") (pintype "bidirectional"))
    )
    (net (code "83") (name "unconnected-(CVOUT-3-PadP$2)") (class "Default")
      (node (ref "CVOUT") (pin "P$2") (pinfunction "3_P$2") (pintype "passive"))
    )
    (net (code "84") (name "unconnected-(GATE1-3-PadP$2)") (class "Default")
      (node (ref "GATE1") (pin "P$2") (pinfunction "3_P$2") (pintype "passive"))
    )
    (net (code "85") (name "unconnected-(GATE2-3-PadP$2)") (class "Default")
      (node (ref "GATE2") (pin "P$2") (pinfunction "3_P$2") (pintype "passive"))
    )
    (net (code "86") (name "unconnected-(GATE3-3-PadP$2)") (class "Default")
      (node (ref "GATE3") (pin "P$2") (pinfunction "3_P$2") (pintype "passive"))
    )
    (net (code "87") (name "unconnected-(IC1-CV-Pad5)") (class "Default")
      (node (ref "IC1") (pin "5") (pinfunction "CV_5") (pintype "input"))
    )
    (net (code "88") (name "unconnected-(IC3-CV-Pad5)") (class "Default")
      (node (ref "IC3") (pin "5") (pinfunction "CV_5") (pintype "input"))
    )
    (net (code "89") (name "unconnected-(J1-Pad3)") (class "Default")
      (node (ref "J1") (pin "3") (pinfunction "3_3") (pintype "passive"))
    )
    (net (code "90") (name "unconnected-(J4-Pad1)") (class "Default")
      (node (ref "J4") (pin "1") (pinfunction "1_1") (pintype "passive"))
    )
    (net (code "91") (name "unconnected-(J4-Pad2)") (class "Default")
      (node (ref "J4") (pin "2") (pinfunction "2_2") (pintype "passive"))
    )
    (net (code "92") (name "unconnected-(J6-Pad3)") (class "Default")
      (node (ref "J6") (pin "3") (pinfunction "3_3") (pintype "passive"))
    )
    (net (code "93") (name "unconnected-(J14-Pad3)") (class "Default")
      (node (ref "J14") (pin "3") (pinfunction "3_3") (pintype "passive"))
    )
    (net (code "94") (name "unconnected-(J14-Pad4)") (class "Default")
      (node (ref "J14") (pin "4") (pinfunction "4_4") (pintype "passive"))
    )
    (net (code "95") (name "unconnected-(J14-Pad5)") (class "Default")
      (node (ref "J14") (pin "5") (pinfunction "5_5") (pintype "passive"))
    )
    (net (code "96") (name "unconnected-(NOTE1-3-PadP$2)") (class "Default")
      (node (ref "NOTE1") (pin "P$2") (pinfunction "3_P$2") (pintype "passive"))
    )
    (net (code "97") (name "unconnected-(NOTE2-3-PadP$2)") (class "Default")
      (node (ref "NOTE2") (pin "P$2") (pinfunction "3_P$2") (pintype "passive"))
    )
    (net (code "98") (name "unconnected-(NOTE3-3-PadP$2)") (class "Default")
      (node (ref "NOTE3") (pin "P$2") (pinfunction "3_P$2") (pintype "passive"))
    )
    (net (code "99") (name "unconnected-(PROBES-3-PadP$2)") (class "Default")
      (node (ref "PROBES") (pin "P$2") (pinfunction "3_P$2") (pintype "passive"))
    )
    (net (code "100") (name "unconnected-(RAWOUT-3-PadP$2)") (class "Default")
      (node (ref "RAWOUT") (pin "P$2") (pinfunction "3_P$2") (pintype "passive"))
    )
    (net (code "101") (name "unconnected-(TP3-PadTP)") (class "Default")
      (node (ref "TP3") (pin "TP") (pinfunction "TP_TP") (pintype "input"))
    )
    (net (code "102") (name "unconnected-(TP4-PadTP)") (class "Default")
      (node (ref "TP4") (pin "TP") (pinfunction "TP_TP") (pintype "input"))
    )
    (net (code "103") (name "unconnected-(TP5-PadTP)") (class "Default")
      (node (ref "TP5") (pin "TP") (pinfunction "TP_TP") (pintype "input"))
    )
    (net (code "104") (name "unconnected-(TP6-PadTP)") (class "Default")
      (node (ref "TP6") (pin "TP") (pinfunction "TP_TP") (pintype "input"))
    )
  )
)
